# ep2c5_128K_SD.net
KiCad netlist of a schematic drawn in EAGLE
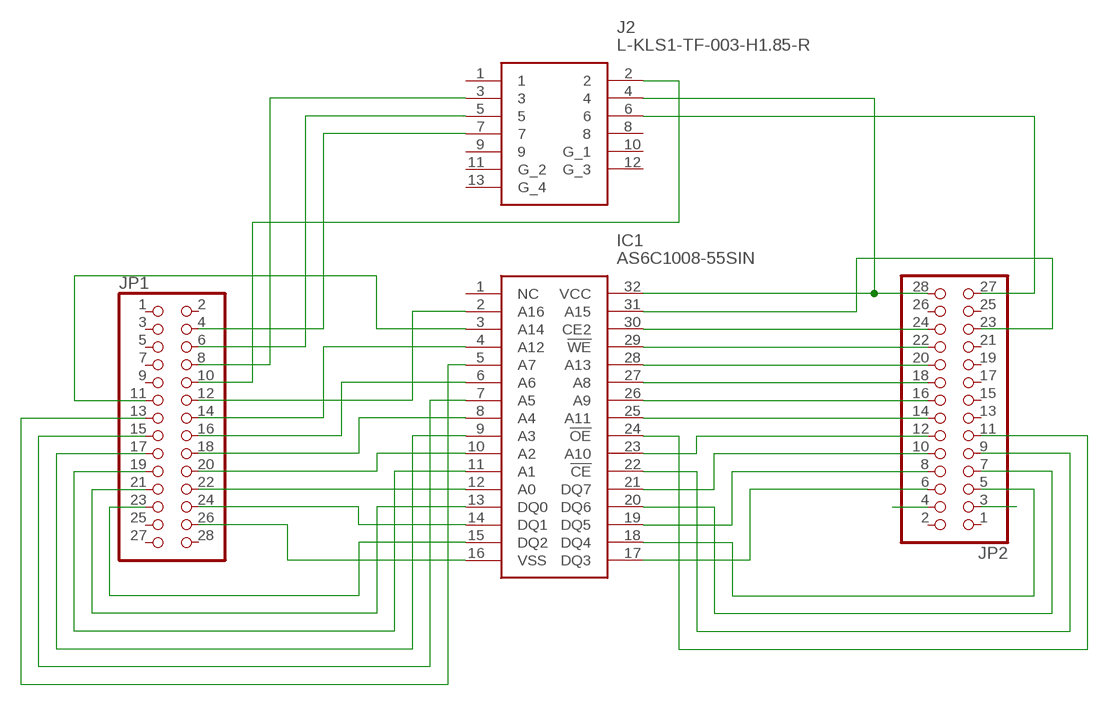
[diagram p0: schematic, sheet 1]

(export (version "E")
  (design (tool "Eeschema 10.0.6"))
  (components
    (comp (ref "IC1")
      (value "AS6C1008-55SIN")
      (footprint "eagle-import:SOIC127P1407X299-32N")
      (fields
        (field (name "MOUSER_PART_NUMBER") "913-AS6C1008-55SIN")
        (field (name "RS_PART_NUMBER") "0538170")
      )
      (libsource (lib "eagle-import") (part "AS6C1008-55SIN"))
    )
    (comp (ref "J2")
      (value "L-KLS1-TF-003-H1.85-R")
      (footprint "eagle-import:L-KLS1-TF-003-H1.85-R")
      (libsource (lib "eagle-import") (part "L-KLS1-TF-003-H1.85-R"))
    )
    (comp (ref "JP1")
      (value "PINHD-2X14")
      (footprint "eagle-import:2X14")
      (libsource (lib "eagle-import") (part "PINHD-2X14"))
    )
    (comp (ref "JP2")
      (value "PINHD-2X14")
      (footprint "eagle-import:2X14")
      (libsource (lib "eagle-import") (part "PINHD-2X14"))
    )
  )
  (nets
    (net (code "1") (name "Net-(IC1-A0)") (class "Default")
      (node (ref "IC1") (pin "12") (pinfunction "A0_12") (pintype "bidirectional"))
      (node (ref "JP1") (pin "22") (pinfunction "22_22") (pintype "passive"))
    )
    (net (code "2") (name "Net-(IC1-A1)") (class "Default")
      (node (ref "IC1") (pin "11") (pinfunction "A1_11") (pintype "bidirectional"))
      (node (ref "JP1") (pin "19") (pinfunction "19_19") (pintype "passive"))
    )
    (net (code "3") (name "Net-(IC1-A2)") (class "Default")
      (node (ref "IC1") (pin "10") (pinfunction "A2_10") (pintype "bidirectional"))
      (node (ref "JP1") (pin "20") (pinfunction "20_20") (pintype "passive"))
    )
    (net (code "4") (name "Net-(IC1-A3)") (class "Default")
      (node (ref "IC1") (pin "9") (pinfunction "A3_9") (pintype "bidirectional"))
      (node (ref "JP1") (pin "17") (pinfunction "17_17") (pintype "passive"))
    )
    (net (code "5") (name "Net-(IC1-A4)") (class "Default")
      (node (ref "IC1") (pin "8") (pinfunction "A4_8") (pintype "bidirectional"))
      (node (ref "JP1") (pin "18") (pinfunction "18_18") (pintype "passive"))
    )
    (net (code "6") (name "Net-(IC1-A5)") (class "Default")
      (node (ref "IC1") (pin "7") (pinfunction "A5_7") (pintype "bidirectional"))
      (node (ref "JP1") (pin "15") (pinfunction "15_15") (pintype "passive"))
    )
    (net (code "7") (name "Net-(IC1-A6)") (class "Default")
      (node (ref "IC1") (pin "6") (pinfunction "A6_6") (pintype "bidirectional"))
      (node (ref "JP1") (pin "16") (pinfunction "16_16") (pintype "passive"))
    )
    (net (code "8") (name "Net-(IC1-A7)") (class "Default")
      (node (ref "IC1") (pin "5") (pinfunction "A7_5") (pintype "bidirectional"))
      (node (ref "JP1") (pin "13") (pinfunction "13_13") (pintype "passive"))
    )
    (net (code "9") (name "Net-(IC1-A8)") (class "Default")
      (node (ref "IC1") (pin "27") (pinfunction "A8_27") (pintype "bidirectional"))
      (node (ref "JP2") (pin "18") (pinfunction "18_18") (pintype "passive"))
    )
    (net (code "10") (name "Net-(IC1-A9)") (class "Default")
      (node (ref "IC1") (pin "26") (pinfunction "A9_26") (pintype "bidirectional"))
      (node (ref "JP2") (pin "16") (pinfunction "16_16") (pintype "passive"))
    )
    (net (code "11") (name "Net-(IC1-A10)") (class "Default")
      (node (ref "IC1") (pin "23") (pinfunction "A10_23") (pintype "bidirectional"))
      (node (ref "JP2") (pin "12") (pinfunction "12_12") (pintype "passive"))
    )
    (net (code "12") (name "Net-(IC1-A11)") (class "Default")
      (node (ref "IC1") (pin "25") (pinfunction "A11_25") (pintype "bidirectional"))
      (node (ref "JP2") (pin "14") (pinfunction "14_14") (pintype "passive"))
    )
    (net (code "13") (name "Net-(IC1-A12)") (class "Default")
      (node (ref "IC1") (pin "4") (pinfunction "A12_4") (pintype "bidirectional"))
      (node (ref "JP1") (pin "14") (pinfunction "14_14") (pintype "passive"))
    )
    (net (code "14") (name "Net-(IC1-A13)") (class "Default")
      (node (ref "IC1") (pin "28") (pinfunction "A13_28") (pintype "bidirectional"))
      (node (ref "JP2") (pin "20") (pinfunction "20_20") (pintype "passive"))
    )
    (net (code "15") (name "Net-(IC1-A14)") (class "Default")
      (node (ref "IC1") (pin "3") (pinfunction "A14_3") (pintype "bidirectional"))
      (node (ref "JP1") (pin "11") (pinfunction "11_11") (pintype "passive"))
    )
    (net (code "16") (name "Net-(IC1-A15)") (class "Default")
      (node (ref "IC1") (pin "31") (pinfunction "A15_31") (pintype "bidirectional"))
      (node (ref "JP2") (pin "23") (pinfunction "23_23") (pintype "passive"))
    )
    (net (code "17") (name "Net-(IC1-A16)") (class "Default")
      (node (ref "IC1") (pin "2") (pinfunction "A16_2") (pintype "bidirectional"))
      (node (ref "JP1") (pin "12") (pinfunction "12_12") (pintype "passive"))
    )
    (net (code "18") (name "Net-(IC1-CE2)") (class "Default")
      (node (ref "IC1") (pin "30") (pinfunction "CE2_30") (pintype "bidirectional"))
      (node (ref "JP2") (pin "24") (pinfunction "24_24") (pintype "passive"))
    )
    (net (code "19") (name "Net-(IC1-DQ0)") (class "Default")
      (node (ref "IC1") (pin "13") (pinfunction "DQ0_13") (pintype "bidirectional"))
      (node (ref "JP1") (pin "21") (pinfunction "21_21") (pintype "passive"))
    )
    (net (code "20") (name "Net-(IC1-DQ1)") (class "Default")
      (node (ref "IC1") (pin "14") (pinfunction "DQ1_14") (pintype "bidirectional"))
      (node (ref "JP1") (pin "24") (pinfunction "24_24") (pintype "passive"))
    )
    (net (code "21") (name "Net-(IC1-DQ2)") (class "Default")
      (node (ref "IC1") (pin "15") (pinfunction "DQ2_15") (pintype "bidirectional"))
      (node (ref "JP1") (pin "23") (pinfunction "23_23") (pintype "passive"))
    )
    (net (code "22") (name "Net-(IC1-DQ3)") (class "Default")
      (node (ref "IC1") (pin "17") (pinfunction "DQ3_17") (pintype "bidirectional"))
      (node (ref "JP2") (pin "6") (pinfunction "6_6") (pintype "passive"))
    )
    (net (code "23") (name "Net-(IC1-DQ4)") (class "Default")
      (node (ref "IC1") (pin "18") (pinfunction "DQ4_18") (pintype "bidirectional"))
      (node (ref "JP2") (pin "5") (pinfunction "5_5") (pintype "passive"))
    )
    (net (code "24") (name "Net-(IC1-DQ5)") (class "Default")
      (node (ref "IC1") (pin "19") (pinfunction "DQ5_19") (pintype "bidirectional"))
      (node (ref "JP2") (pin "8") (pinfunction "8_8") (pintype "passive"))
    )
    (net (code "25") (name "Net-(IC1-DQ6)") (class "Default")
      (node (ref "IC1") (pin "20") (pinfunction "DQ6_20") (pintype "bidirectional"))
      (node (ref "JP2") (pin "7") (pinfunction "7_7") (pintype "passive"))
    )
    (net (code "26") (name "Net-(IC1-DQ7)") (class "Default")
      (node (ref "IC1") (pin "21") (pinfunction "DQ7_21") (pintype "bidirectional"))
      (node (ref "JP2") (pin "10") (pinfunction "10_10") (pintype "passive"))
    )
    (net (code "27") (name "Net-(IC1-VCC)") (class "Default")
      (node (ref "IC1") (pin "32") (pinfunction "VCC_32") (pintype "bidirectional"))
      (node (ref "J2") (pin "4") (pinfunction "4_4") (pintype "bidirectional"))
      (node (ref "JP2") (pin "28") (pinfunction "28_28") (pintype "passive"))
    )
    (net (code "28") (name "Net-(IC1-VSS)") (class "Default")
      (node (ref "IC1") (pin "16") (pinfunction "VSS_16") (pintype "bidirectional"))
      (node (ref "JP1") (pin "26") (pinfunction "26_26") (pintype "passive"))
    )
    (net (code "29") (name "Net-(IC1-~{CE})") (class "Default")
      (node (ref "IC1") (pin "22") (pinfunction "~{CE}_22") (pintype "bidirectional"))
      (node (ref "JP2") (pin "9") (pinfunction "9_9") (pintype "passive"))
    )
    (net (code "30") (name "Net-(IC1-~{OE})") (class "Default")
      (node (ref "IC1") (pin "24") (pinfunction "~{OE}_24") (pintype "bidirectional"))
      (node (ref "JP2") (pin "11") (pinfunction "11_11") (pintype "passive"))
    )
    (net (code "31") (name "Net-(IC1-~{WE})") (class "Default")
      (node (ref "IC1") (pin "29") (pinfunction "~{WE}_29") (pintype "bidirectional"))
      (node (ref "JP2") (pin "22") (pinfunction "22_22") (pintype "passive"))
    )
    (net (code "32") (name "Net-(J2-Pad2)") (class "Default")
      (node (ref "J2") (pin "2") (pinfunction "2_2") (pintype "bidirectional"))
      (node (ref "JP1") (pin "10") (pinfunction "10_10") (pintype "passive"))
    )
    (net (code "33") (name "Net-(J2-Pad3)") (class "Default")
      (node (ref "J2") (pin "3") (pinfunction "3_3") (pintype "bidirectional"))
      (node (ref "JP1") (pin "8") (pinfunction "8_8") (pintype "passive"))
    )
    (net (code "34") (name "Net-(J2-Pad5)") (class "Default")
      (node (ref "J2") (pin "5") (pinfunction "5_5") (pintype "bidirectional"))
      (node (ref "JP1") (pin "6") (pinfunction "6_6") (pintype "passive"))
    )
    (net (code "35") (name "Net-(J2-Pad6)") (class "Default")
      (node (ref "J2") (pin "6") (pinfunction "6_6") (pintype "bidirectional"))
      (node (ref "JP2") (pin "27") (pinfunction "27_27") (pintype "passive"))
    )
    (net (code "36") (name "Net-(J2-Pad7)") (class "Default")
      (node (ref "J2") (pin "7") (pinfunction "7_7") (pintype "bidirectional"))
      (node (ref "JP1") (pin "4") (pinfunction "4_4") (pintype "passive"))
    )
    (net (code "37") (name "unconnected-(IC1-NC-Pad1)") (class "Default")
      (node (ref "IC1") (pin "1") (pinfunction "NC_1") (pintype "no_connect"))
    )
    (net (code "38") (name "unconnected-(J2-G_1-Pad10)") (class "Default")
      (node (ref "J2") (pin "10") (pinfunction "G_1_10") (pintype "bidirectional"))
    )
    (net (code "39") (name "unconnected-(J2-G_2-Pad11)") (class "Default")
      (node (ref "J2") (pin "11") (pinfunction "G_2_11") (pintype "bidirectional"))
    )
    (net (code "40") (name "unconnected-(J2-G_3-Pad12)") (class "Default")
      (node (ref "J2") (pin "12") (pinfunction "G_3_12") (pintype "bidirectional"))
    )
    (net (code "41") (name "unconnected-(J2-G_4-Pad13)") (class "Default")
      (node (ref "J2") (pin "13") (pinfunction "G_4_13") (pintype "bidirectional"))
    )
    (net (code "42") (name "unconnected-(J2-Pad1)") (class "Default")
      (node (ref "J2") (pin "1") (pinfunction "1_1") (pintype "bidirectional"))
    )
    (net (code "43") (name "unconnected-(J2-Pad8)") (class "Default")
      (node (ref "J2") (pin "8") (pinfunction "8_8") (pintype "bidirectional"))
    )
    (net (code "44") (name "unconnected-(J2-Pad9)") (class "Default")
      (node (ref "J2") (pin "9") (pinfunction "9_9") (pintype "bidirectional"))
    )
    (net (code "45") (name "unconnected-(JP1-Pad1)") (class "Default")
      (node (ref "JP1") (pin "1") (pinfunction "1_1") (pintype "passive"))
    )
    (net (code "46") (name "unconnected-(JP1-Pad2)") (class "Default")
      (node (ref "JP1") (pin "2") (pinfunction "2_2") (pintype "passive"))
    )
    (net (code "47") (name "unconnected-(JP1-Pad3)") (class "Default")
      (node (ref "JP1") (pin "3") (pinfunction "3_3") (pintype "passive"))
    )
    (net (code "48") (name "unconnected-(JP1-Pad5)") (class "Default")
      (node (ref "JP1") (pin "5") (pinfunction "5_5") (pintype "passive"))
    )
    (net (code "49") (name "unconnected-(JP1-Pad7)") (class "Default")
      (node (ref "JP1") (pin "7") (pinfunction "7_7") (pintype "passive"))
    )
    (net (code "50") (name "unconnected-(JP1-Pad9)") (class "Default")
      (node (ref "JP1") (pin "9") (pinfunction "9_9") (pintype "passive"))
    )
    (net (code "51") (name "unconnected-(JP1-Pad25)") (class "Default")
      (node (ref "JP1") (pin "25") (pinfunction "25_25") (pintype "passive"))
    )
    (net (code "52") (name "unconnected-(JP1-Pad27)") (class "Default")
      (node (ref "JP1") (pin "27") (pinfunction "27_27") (pintype "passive"))
    )
    (net (code "53") (name "unconnected-(JP1-Pad28)") (class "Default")
      (node (ref "JP1") (pin "28") (pinfunction "28_28") (pintype "passive"))
    )
    (net (code "54") (name "unconnected-(JP2-Pad1)") (class "Default")
      (node (ref "JP2") (pin "1") (pinfunction "1_1") (pintype "passive"))
    )
    (net (code "55") (name "unconnected-(JP2-Pad2)") (class "Default")
      (node (ref "JP2") (pin "2") (pinfunction "2_2") (pintype "passive"))
    )
    (net (code "56") (name "unconnected-(JP2-Pad3)") (class "Default")
      (node (ref "JP2") (pin "3") (pinfunction "3_3") (pintype "passive"))
    )
    (net (code "57") (name "unconnected-(JP2-Pad4)") (class "Default")
      (node (ref "JP2") (pin "4") (pinfunction "4_4") (pintype "passive"))
    )
    (net (code "58") (name "unconnected-(JP2-Pad13)") (class "Default")
      (node (ref "JP2") (pin "13") (pinfunction "13_13") (pintype "passive"))
    )
    (net (code "59") (name "unconnected-(JP2-Pad15)") (class "Default")
      (node (ref "JP2") (pin "15") (pinfunction "15_15") (pintype "passive"))
    )
    (net (code "60") (name "unconnected-(JP2-Pad17)") (class "Default")
      (node (ref "JP2") (pin "17") (pinfunction "17_17") (pintype "passive"))
    )
    (net (code "61") (name "unconnected-(JP2-Pad19)") (class "Default")
      (node (ref "JP2") (pin "19") (pinfunction "19_19") (pintype "passive"))
    )
    (net (code "62") (name "unconnected-(JP2-Pad21)") (class "Default")
      (node (ref "JP2") (pin "21") (pinfunction "21_21") (pintype "passive"))
    )
    (net (code "63") (name "unconnected-(JP2-Pad25)") (class "Default")
      (node (ref "JP2") (pin "25") (pinfunction "25_25") (pintype "passive"))
    )
    (net (code "64") (name "unconnected-(JP2-Pad26)") (class "Default")
      (node (ref "JP2") (pin "26") (pinfunction "26_26") (pintype "passive"))
    )
  )
)
